# Speed_Controller_v1_0.net
KiCad netlist of a schematic drawn in EAGLE
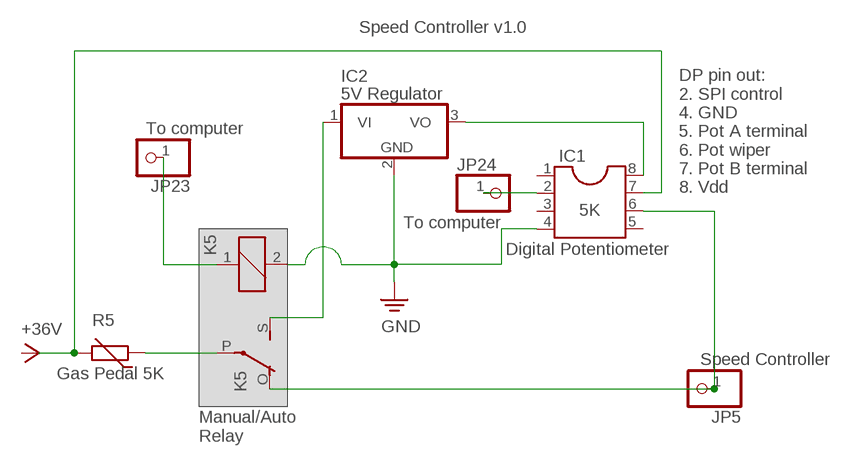
[diagram p0: schematic, sheet 1]

(export (version "E")
  (design (tool "Eeschema 10.0.6"))
  (components
    (comp (ref "IC1")
      (value "Digital Potentiometer")
      (footprint "eagle-import:DIL08")
      (libsource (lib "eagle-import") (part "DIL8"))
    )
    (comp (ref "IC2")
      (value "5V Regulator")
      (footprint "eagle-import:TO220H")
      (libsource (lib "eagle-import") (part "78T05"))
    )
    (comp (ref "JP5")
      (value "Speed Controller")
      (footprint "eagle-import:1X01")
      (libsource (lib "eagle-import") (part "PINHD-1X1"))
    )
    (comp (ref "JP23")
      (value "To computer")
      (footprint "eagle-import:1X01")
      (libsource (lib "eagle-import") (part "PINHD-1X1"))
    )
    (comp (ref "JP24")
      (value "To computer")
      (footprint "eagle-import:1X01")
      (libsource (lib "eagle-import") (part "PINHD-1X1"))
    )
    (comp (ref "K5")
      (value "G2R")
      (footprint "eagle-import:G2R")
      (libsource (lib "eagle-import") (part "G2R"))
    )
    (comp (ref "R5")
      (value "Gas Pedal 5K")
      (footprint "eagle-import:R-5")
      (libsource (lib "eagle-import") (part "THERMISTOR_R-5"))
    )
  )
  (nets
    (net (code "2") (name "GND") (class "Default")
      (node (ref "IC1") (pin "4") (pinfunction "4_4") (pintype "passive"))
      (node (ref "IC2") (pin "2") (pinfunction "GND_2") (pintype "passive"))
      (node (ref "K5") (pin "2") (pinfunction "2_2") (pintype "passive"))
    )
    (net (code "3") (name "Net-(IC1-Pad2)") (class "Default")
      (node (ref "IC1") (pin "2") (pinfunction "2_2") (pintype "passive"))
      (node (ref "JP24") (pin "1") (pinfunction "1_1") (pintype "passive"))
    )
    (net (code "4") (name "Net-(IC1-Pad6)") (class "Default")
      (node (ref "IC1") (pin "6") (pinfunction "6_6") (pintype "passive"))
      (node (ref "JP5") (pin "1") (pinfunction "1_1") (pintype "passive"))
      (node (ref "K5") (pin "O") (pinfunction "O_O") (pintype "passive"))
    )
    (net (code "5") (name "Net-(IC1-Pad7)") (class "Default")
      (node (ref "IC1") (pin "7") (pinfunction "7_7") (pintype "passive"))
      (node (ref "R5") (pin "2") (pinfunction "2_2") (pintype "passive"))
    )
    (net (code "6") (name "Net-(IC2-VI)") (class "Default")
      (node (ref "IC2") (pin "1") (pinfunction "VI_1") (pintype "input"))
      (node (ref "K5") (pin "S") (pinfunction "S_S") (pintype "passive"))
    )
    (net (code "7") (name "Net-(IC2-VO)") (class "Default")
      (node (ref "IC1") (pin "8") (pinfunction "8_8") (pintype "passive"))
      (node (ref "IC2") (pin "3") (pinfunction "VO_3") (pintype "passive"))
    )
    (net (code "8") (name "Net-(JP23-Pad1)") (class "Default")
      (node (ref "JP23") (pin "1") (pinfunction "1_1") (pintype "passive"))
      (node (ref "K5") (pin "1") (pinfunction "1_1") (pintype "passive"))
    )
    (net (code "9") (name "Net-(K5-PadP)") (class "Default")
      (node (ref "K5") (pin "P") (pinfunction "P_P") (pintype "passive"))
      (node (ref "R5") (pin "1") (pinfunction "1_1") (pintype "passive"))
    )
    (net (code "10") (name "unconnected-(IC1-Pad1)") (class "Default")
      (node (ref "IC1") (pin "1") (pinfunction "1_1") (pintype "passive"))
    )
    (net (code "11") (name "unconnected-(IC1-Pad3)") (class "Default")
      (node (ref "IC1") (pin "3") (pinfunction "3_3") (pintype "passive"))
    )
    (net (code "12") (name "unconnected-(IC1-Pad5)") (class "Default")
      (node (ref "IC1") (pin "5") (pinfunction "5_5") (pintype "passive"))
    )
  )
)
